# Power_Supply.net
KiCad netlist of a schematic drawn in Altium Designer
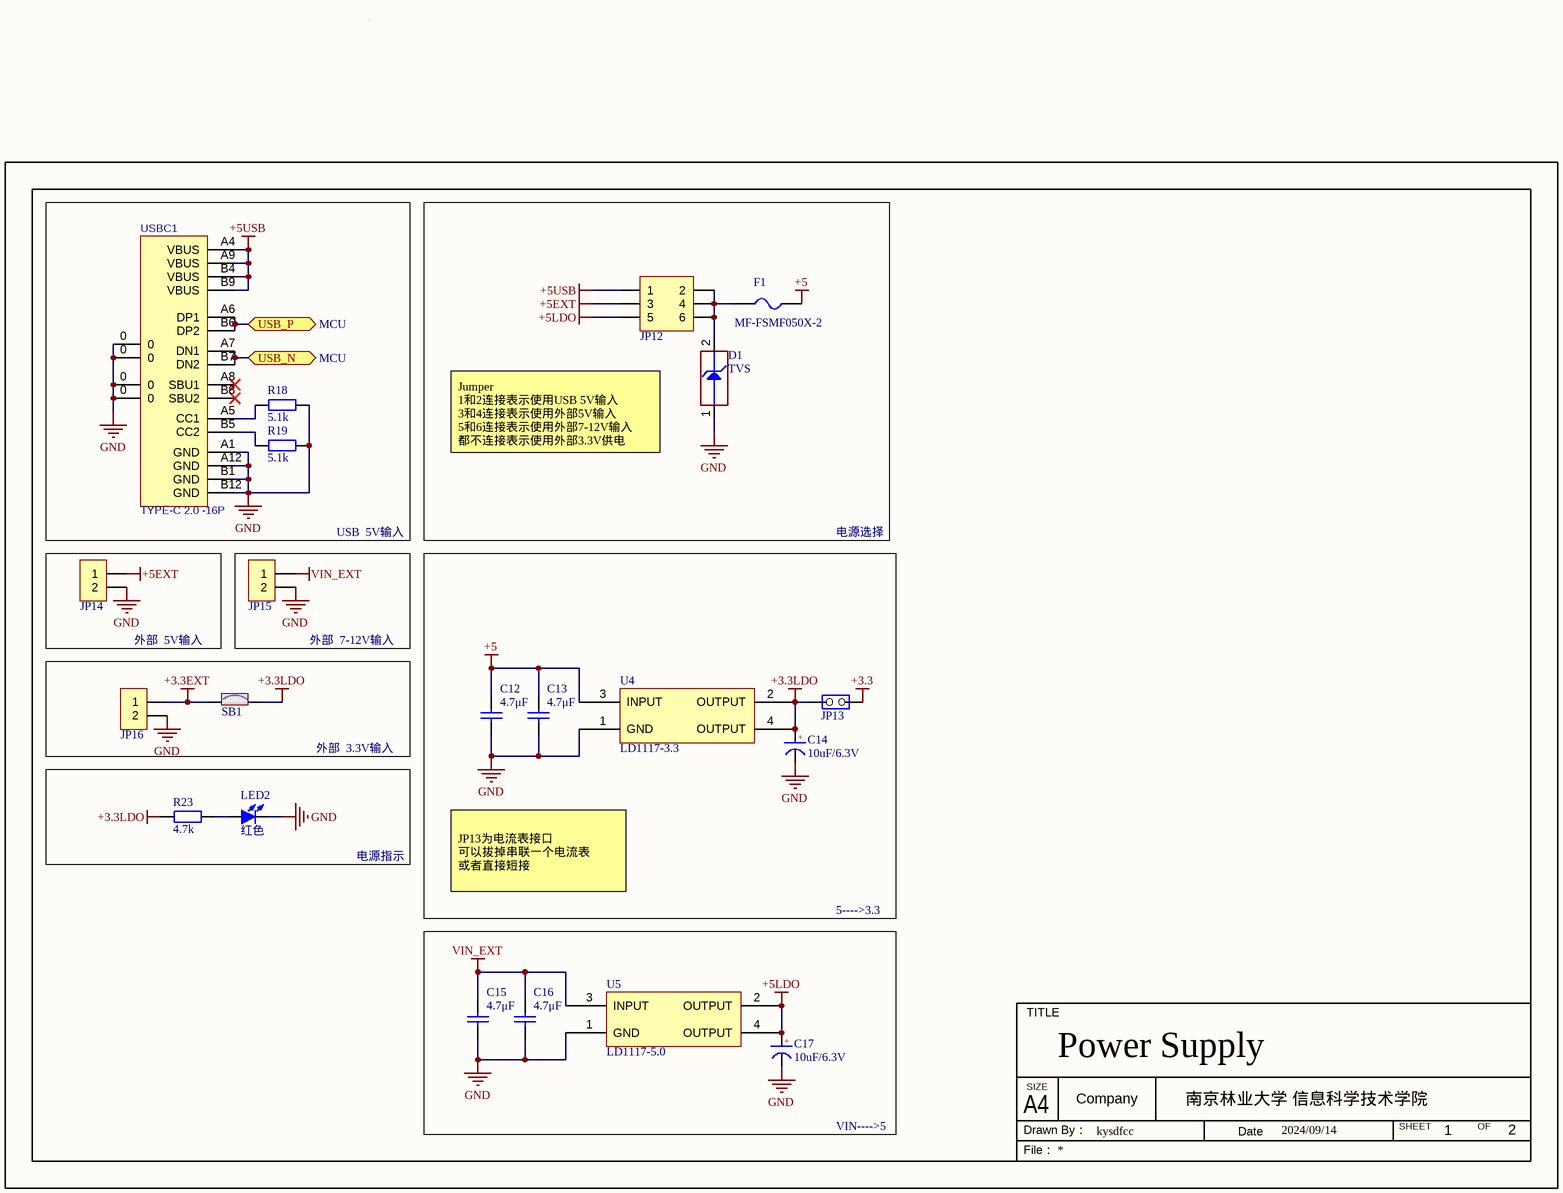
[diagram p0: Power_Supply.SchDoc]

(export (version "E")
  (design (tool "Eeschema 10.0.6"))
  (components
    (comp (ref "C12")
      (value "4.7μF")
      (footprint "C 0603_L")
      (description "贴片电容")
      (libsource (lib "0.1 - 电阻-电容-电感") (part "C"))
    )
    (comp (ref "C13")
      (value "4.7μF")
      (footprint "C 0603_L")
      (description "贴片电容")
      (libsource (lib "0.1 - 电阻-电容-电感") (part "C"))
    )
    (comp (ref "C14")
      (value "10uF/6.3V")
      (footprint "CD A(3216)")
      (description "贴片钽电容")
      (libsource (lib "0.1 - 电阻-电容-电感") (part "CT"))
    )
    (comp (ref "C15")
      (value "4.7μF")
      (footprint "C 0603_L")
      (description "贴片电容")
      (libsource (lib "0.1 - 电阻-电容-电感") (part "C"))
    )
    (comp (ref "C16")
      (value "4.7μF")
      (footprint "C 0603_L")
      (description "贴片电容")
      (libsource (lib "0.1 - 电阻-电容-电感") (part "C"))
    )
    (comp (ref "C17")
      (value "10uF/6.3V")
      (footprint "CD A(3216)")
      (description "贴片钽电容")
      (libsource (lib "0.1 - 电阻-电容-电感") (part "CT"))
    )
    (comp (ref "D1")
      (value "TVS")
      (footprint "SOD-123")
      (description "High power Transient voltage suppressor:25V/35A EOS and ESD transients protection.")
      (fields
        (field (name "INTERNAL_PART_NUMBER") "MCD-01207")
        (field (name "MANUFACTURER_PART_NUMBER") "ESDA25P35-1U1M")
        (field (name "PROVIDED_BY") "SUBCO with ST control")
      )
      (libsource (lib "Schlib1") (part "TVS"))
    )
    (comp (ref "F1")
      (value "MF-FSMF050X-2")
      (footprint "FU 0603")
      (description "贴片保险丝")
      (libsource (lib "2.0 - 保险丝-晶振-光耦") (part "FU"))
    )
    (comp (ref "JP12")
      (value "Header3X2")
      (footprint "HDR2.54-LI-2x3P")
      (description "3*2P接插件")
      (libsource (lib "5.4 - 接插件-脚距2.54 (100mil) ") (part "Header 3X2"))
    )
    (comp (ref "JP13")
      (value "Jumper_Header 2x1")
      (footprint "CON_SAMTEC_TSW-102-07-G-S")
      (description "Header, 2x1, 2,54mm, VR, TH, Height 5.84mm/2.54mm")
      (fields (field (name "INTERNAL_PART_NUMBER") "MCD-00045") (field (name "MANUFACTURER") "SAMTEC"))
      (libsource (lib "Schlib1") (part "Header 2x1"))
    )
    (comp (ref "JP14")
      (value "HDR-1X2")
      (footprint "HDR2.54-LI-2P")
      (description "2P接插件")
      (libsource (lib "5.4 - 接插件-脚距2.54 (100mil) ") (part "Header 2"))
    )
    (comp (ref "JP15")
      (value "HDR-1X2")
      (footprint "HDR2.54-LI-2P")
      (description "2P接插件")
      (libsource (lib "5.4 - 接插件-脚距2.54 (100mil) ") (part "Header 2"))
    )
    (comp (ref "JP16")
      (value "HDR-1X2")
      (footprint "HDR2.54-LI-2P")
      (description "2P接插件")
      (libsource (lib "5.4 - 接插件-脚距2.54 (100mil) ") (part "Header 2"))
    )
    (comp (ref "LED2")
      (value "红色")
      (footprint "LED 0603R")
      (description "贴片LED")
      (libsource (lib "0.3 - LED发光二极管") (part "LED-SMD"))
    )
    (comp (ref "R18")
      (value "5.1k")
      (footprint "R 0603_L")
      (description "贴片电阻")
      (libsource (lib "0.1 - 电阻-电容-电感") (part "R"))
    )
    (comp (ref "R19")
      (value "5.1k")
      (footprint "R 0603_L")
      (description "贴片电阻")
      (libsource (lib "0.1 - 电阻-电容-电感") (part "R"))
    )
    (comp (ref "R23")
      (value "4.7k")
      (footprint "R 0603_L")
      (description "贴片电阻")
      (libsource (lib "0.1 - 电阻-电容-电感") (part "R"))
    )
    (comp (ref "SB1")
      (value "SB_ON")
      (footprint "SOLDER-BRIDGE_R0603-0R")
      (description "Solder Bridge ON")
      (fields
        (field (name "INTERNAL_PART_NUMBER") "MCD-00071")
        (field (name "MANUFACTURER_PART_NUMBER") "RC0603JR-070RL")
        (field (name "PROVIDED_BY") "SUBCO")
      )
      (libsource (lib "Schlib1") (part "Solder Bridge"))
    )
    (comp (ref "U4")
      (value "LD1117-3.3")
      (footprint "LM1117 SOT223")
      (libsource (lib "Schlib1") (part "LD1117"))
    )
    (comp (ref "U5")
      (value "LD1117-5.0")
      (footprint "LM1117 SOT223")
      (libsource (lib "Schlib1") (part "LD1117"))
    )
    (comp (ref "USBC1")
      (value "TYPE-C 2.0 -16P")
      (footprint "USB-C-SMD_TYPE-C-USB-5")
      (description "USB2.0 Type-C 母座 16Pin")
      (libsource (lib "0.8 - 以太网-音频-USB插座") (part "USB2.0 Type-C 16Pin母座"))
    )
  )
  (nets
    (net (code "1") (name "+3.3") (class "Default")
      (node (ref "JP13") (pin "2") (pinfunction "NO_2") (pintype "passive"))
    )
    (net (code "2") (name "+3.3EXT") (class "Default")
      (node (ref "JP16") (pin "1") (pinfunction "1_1") (pintype "passive"))
      (node (ref "SB1") (pin "1") (pinfunction "1_1") (pintype "passive"))
    )
    (net (code "3") (name "+3.3LDO") (class "Default")
      (node (ref "C14") (pin "1") (pinfunction "A_1") (pintype "passive"))
      (node (ref "JP13") (pin "1") (pinfunction "COMMON_1") (pintype "passive"))
      (node (ref "R23") (pin "2") (pinfunction "2_2") (pintype "passive"))
      (node (ref "SB1") (pin "2") (pinfunction "2_2") (pintype "passive"))
      (node (ref "U4") (pin "2") (pinfunction "OUTPUT_2") (pintype "passive"))
      (node (ref "U4") (pin "4") (pinfunction "OUTPUT_4") (pintype "passive"))
    )
    (net (code "4") (name "+5") (class "Default")
      (node (ref "C12") (pin "2") (pinfunction "2_2") (pintype "passive"))
      (node (ref "C13") (pin "2") (pinfunction "2_2") (pintype "passive"))
      (node (ref "F1") (pin "2") (pinfunction "2_2") (pintype "passive"))
      (node (ref "U4") (pin "3") (pinfunction "INPUT_3") (pintype "passive"))
    )
    (net (code "5") (name "+5EXT") (class "Default")
      (node (ref "JP12") (pin "3") (pinfunction "3_3") (pintype "passive"))
      (node (ref "JP14") (pin "1") (pinfunction "1_1") (pintype "passive"))
    )
    (net (code "6") (name "+5LDO") (class "Default")
      (node (ref "C17") (pin "1") (pinfunction "A_1") (pintype "passive"))
      (node (ref "JP12") (pin "5") (pinfunction "5_5") (pintype "passive"))
      (node (ref "U5") (pin "2") (pinfunction "OUTPUT_2") (pintype "passive"))
      (node (ref "U5") (pin "4") (pinfunction "OUTPUT_4") (pintype "passive"))
    )
    (net (code "7") (name "+5USB") (class "Default")
      (node (ref "JP12") (pin "1") (pinfunction "1_1") (pintype "passive"))
      (node (ref "USBC1") (pin "A4") (pinfunction "VBUS_A4") (pintype "passive"))
      (node (ref "USBC1") (pin "A9") (pinfunction "VBUS_A9") (pintype "passive"))
      (node (ref "USBC1") (pin "B4") (pinfunction "VBUS_B4") (pintype "passive"))
      (node (ref "USBC1") (pin "B9") (pinfunction "VBUS_B9") (pintype "passive"))
    )
    (net (code "8") (name "/USB_N") (class "Default")
      (node (ref "USBC1") (pin "A7") (pinfunction "DN1_A7") (pintype "passive"))
      (node (ref "USBC1") (pin "B7") (pinfunction "DN2_B7") (pintype "passive"))
    )
    (net (code "9") (name "/USB_P") (class "Default")
      (node (ref "USBC1") (pin "A6") (pinfunction "DP1_A6") (pintype "passive"))
      (node (ref "USBC1") (pin "B6") (pinfunction "DP2_B6") (pintype "passive"))
    )
    (net (code "10") (name "GND") (class "Default")
      (node (ref "C12") (pin "1") (pinfunction "1_1") (pintype "passive"))
      (node (ref "C13") (pin "1") (pinfunction "1_1") (pintype "passive"))
      (node (ref "C14") (pin "2") (pinfunction "K_2") (pintype "passive"))
      (node (ref "C15") (pin "1") (pinfunction "1_1") (pintype "passive"))
      (node (ref "C16") (pin "1") (pinfunction "1_1") (pintype "passive"))
      (node (ref "C17") (pin "2") (pinfunction "K_2") (pintype "passive"))
      (node (ref "D1") (pin "1") (pinfunction "IO1_1") (pintype "passive"))
      (node (ref "JP14") (pin "2") (pinfunction "2_2") (pintype "passive"))
      (node (ref "JP15") (pin "2") (pinfunction "2_2") (pintype "passive"))
      (node (ref "JP16") (pin "2") (pinfunction "2_2") (pintype "passive"))
      (node (ref "LED2") (pin "2") (pinfunction "K_2") (pintype "passive"))
      (node (ref "R18") (pin "2") (pinfunction "2_2") (pintype "passive"))
      (node (ref "R19") (pin "2") (pinfunction "2_2") (pintype "passive"))
      (node (ref "U4") (pin "1") (pinfunction "GND_1") (pintype "passive"))
      (node (ref "U5") (pin "1") (pinfunction "GND_1") (pintype "passive"))
      (node (ref "USBC1") (pin "0") (pinfunction "0_0") (pintype "passive"))
      (node (ref "USBC1") (pin "A1") (pinfunction "GND_A1") (pintype "passive"))
      (node (ref "USBC1") (pin "A12") (pinfunction "GND_A12") (pintype "passive"))
      (node (ref "USBC1") (pin "B1") (pinfunction "GND_B1") (pintype "passive"))
      (node (ref "USBC1") (pin "B12") (pinfunction "GND_B12") (pintype "passive"))
    )
    (net (code "11") (name "Net-(D1-GND)") (class "Default")
      (node (ref "D1") (pin "2") (pinfunction "GND_2") (pintype "passive"))
      (node (ref "F1") (pin "1") (pinfunction "1_1") (pintype "passive"))
      (node (ref "JP12") (pin "2") (pinfunction "2_2") (pintype "passive"))
      (node (ref "JP12") (pin "4") (pinfunction "4_4") (pintype "passive"))
      (node (ref "JP12") (pin "6") (pinfunction "6_6") (pintype "passive"))
    )
    (net (code "12") (name "Net-(LED2-A)") (class "Default")
      (node (ref "LED2") (pin "1") (pinfunction "A_1") (pintype "passive"))
      (node (ref "R23") (pin "1") (pinfunction "1_1") (pintype "passive"))
    )
    (net (code "13") (name "Net-(USBC1-CC1)") (class "Default")
      (node (ref "R18") (pin "1") (pinfunction "1_1") (pintype "passive"))
      (node (ref "USBC1") (pin "A5") (pinfunction "CC1_A5") (pintype "passive"))
    )
    (net (code "14") (name "Net-(USBC1-CC2)") (class "Default")
      (node (ref "R19") (pin "1") (pinfunction "1_1") (pintype "passive"))
      (node (ref "USBC1") (pin "B5") (pinfunction "CC2_B5") (pintype "passive"))
    )
    (net (code "15") (name "VIN_EXT") (class "Default")
      (node (ref "C15") (pin "2") (pinfunction "2_2") (pintype "passive"))
      (node (ref "C16") (pin "2") (pinfunction "2_2") (pintype "passive"))
      (node (ref "JP15") (pin "1") (pinfunction "1_1") (pintype "passive"))
      (node (ref "U5") (pin "3") (pinfunction "INPUT_3") (pintype "passive"))
    )
    (net (code "16") (name "unconnected-(USBC1-SBU1-PadA8)") (class "Default")
      (node (ref "USBC1") (pin "A8") (pinfunction "SBU1_A8") (pintype "passive+no_connect"))
    )
    (net (code "17") (name "unconnected-(USBC1-SBU2-PadB8)") (class "Default")
      (node (ref "USBC1") (pin "B8") (pinfunction "SBU2_B8") (pintype "passive+no_connect"))
    )
  )
)
